# GateWay.net
KiCad netlist of a schematic drawn in EAGLE
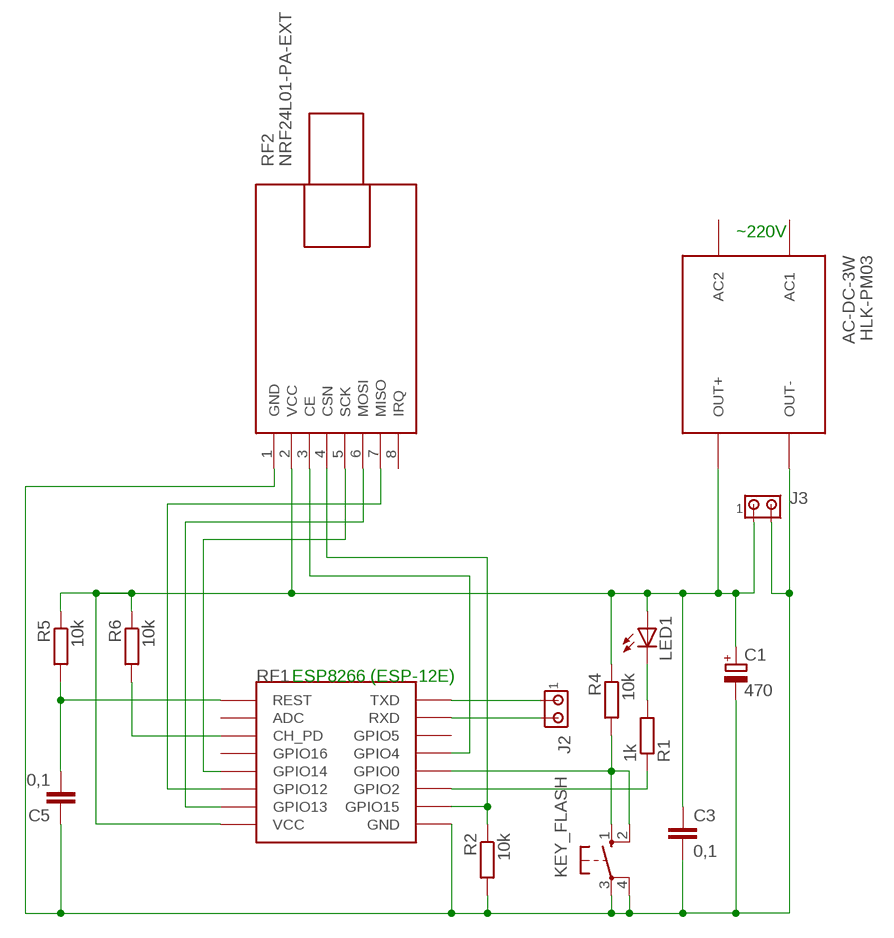
[diagram p0: schematic, sheet 1]

(export (version "E")
  (design (tool "Eeschema 10.0.6"))
  (components
    (comp (ref "C1")
      (value "470")
      (footprint "eagle-import:E2,5-6E")
      (libsource (lib "eagle-import") (part "CPOL-EUE2,5-6E"))
    )
    (comp (ref "C3")
      (value "0,1")
      (footprint "eagle-import:C025-024X044")
      (libsource (lib "eagle-import") (part "C-EU025-024X044"))
    )
    (comp (ref "C5")
      (value "0,1")
      (footprint "eagle-import:C025-025X050")
      (libsource (lib "eagle-import") (part "C-EU025-025X050"))
    )
    (comp (ref "HLK-PM03")
      (value "AC-DC-3W")
      (footprint "eagle-import:AC-DC-3.5W")
      (libsource (lib "eagle-import") (part "AC-DC-3.5W"))
    )
    (comp (ref "J2")
      (value "MTA02-100")
      (footprint "eagle-import:10X02MTA")
      (libsource (lib "eagle-import") (part "MTA02-100"))
    )
    (comp (ref "J3")
      (value "MTA02-100")
      (footprint "eagle-import:10X02MTA")
      (libsource (lib "eagle-import") (part "MTA02-100"))
    )
    (comp (ref "KEY_FLASH")
      (value "10-XX")
      (footprint "eagle-import:B3F-10XX")
      (fields (field (name "MPN") "B3F-1000"))
      (libsource (lib "eagle-import") (part "10-XX"))
    )
    (comp (ref "LED1")
      (value "LED5MM")
      (footprint "eagle-import:LED5MM")
      (libsource (lib "eagle-import") (part "LED5MM"))
    )
    (comp (ref "R1")
      (value "1k")
      (footprint "eagle-import:0204_7")
      (libsource (lib "eagle-import") (part "R-EU_0204/7"))
    )
    (comp (ref "R2")
      (value "10k")
      (footprint "eagle-import:0204_7")
      (libsource (lib "eagle-import") (part "R-EU_0204/7"))
    )
    (comp (ref "R4")
      (value "10k")
      (footprint "eagle-import:0204_7")
      (libsource (lib "eagle-import") (part "R-EU_0204/7"))
    )
    (comp (ref "R5")
      (value "10k")
      (footprint "eagle-import:0207_12")
      (libsource (lib "eagle-import") (part "R-EU_0207/12"))
    )
    (comp (ref "R6")
      (value "10k")
      (footprint "eagle-import:0207_10")
      (libsource (lib "eagle-import") (part "R-EU_0207/10"))
    )
    (comp (ref "RF1")
      (value "ESP")
      (footprint "eagle-import:ESP12E-SMD")
      (libsource (lib "eagle-import") (part "ESP12ESMD"))
    )
    (comp (ref "RF2")
      (value "NRF24L01-PA-EXT")
      (footprint "eagle-import:WIRELESS-NRF24L01-PA-EXT")
      (libsource (lib "eagle-import") (part "WIRELESS-NRF24L01-PA-EXT"))
    )
  )
  (nets
    (net (code "1") (name "Net-(HLK-PM03-OUT+)") (class "Default")
      (node (ref "C1") (pin "+") (pinfunction "+_+") (pintype "passive"))
      (node (ref "C3") (pin "1") (pinfunction "1_1") (pintype "passive"))
      (node (ref "HLK-PM03") (pin "J2.3") (pinfunction "OUT+_J2.3") (pintype "bidirectional"))
      (node (ref "J3") (pin "1") (pinfunction "1_1") (pintype "passive"))
      (node (ref "LED1") (pin "A") (pinfunction "A_A") (pintype "passive"))
      (node (ref "R4") (pin "1") (pinfunction "1_1") (pintype "passive"))
      (node (ref "R5") (pin "1") (pinfunction "1_1") (pintype "passive"))
      (node (ref "R6") (pin "1") (pinfunction "1_1") (pintype "passive"))
      (node (ref "RF1") (pin "VCC") (pinfunction "VCC_VCC") (pintype "bidirectional"))
      (node (ref "RF2") (pin "2") (pinfunction "VCC_2") (pintype "power_in"))
    )
    (net (code "2") (name "Net-(HLK-PM03-OUT-)") (class "Default")
      (node (ref "C1") (pin "-") (pinfunction "-_-") (pintype "passive"))
      (node (ref "C3") (pin "2") (pinfunction "2_2") (pintype "passive"))
      (node (ref "C5") (pin "1") (pinfunction "1_1") (pintype "passive"))
      (node (ref "HLK-PM03") (pin "J2.1") (pinfunction "OUT-_J2.1") (pintype "bidirectional"))
      (node (ref "J3") (pin "2") (pinfunction "2_2") (pintype "passive"))
      (node (ref "KEY_FLASH") (pin "3") (pinfunction "P_3") (pintype "passive"))
      (node (ref "KEY_FLASH") (pin "4") (pinfunction "P1_4") (pintype "passive"))
      (node (ref "R2") (pin "2") (pinfunction "2_2") (pintype "passive"))
      (node (ref "RF1") (pin "GND") (pinfunction "GND_GND") (pintype "bidirectional"))
      (node (ref "RF2") (pin "1") (pinfunction "GND_1") (pintype "power_in"))
    )
    (net (code "3") (name "Net-(KEY_FLASH-S)") (class "Default")
      (node (ref "KEY_FLASH") (pin "1") (pinfunction "S_1") (pintype "passive"))
      (node (ref "KEY_FLASH") (pin "2") (pinfunction "S1_2") (pintype "passive"))
      (node (ref "R4") (pin "2") (pinfunction "2_2") (pintype "passive"))
      (node (ref "RF1") (pin "GPIO0") (pinfunction "GPIO0_GPIO0") (pintype "bidirectional"))
    )
    (net (code "4") (name "Net-(LED1-C)") (class "Default")
      (node (ref "LED1") (pin "K") (pinfunction "C_K") (pintype "passive"))
      (node (ref "R1") (pin "2") (pinfunction "2_2") (pintype "passive"))
    )
    (net (code "5") (name "Net-(R1-Pad1)") (class "Default")
      (node (ref "R1") (pin "1") (pinfunction "1_1") (pintype "passive"))
      (node (ref "RF1") (pin "GPIO2") (pinfunction "GPIO2_GPIO2") (pintype "bidirectional"))
    )
    (net (code "6") (name "Net-(R6-Pad2)") (class "Default")
      (node (ref "R6") (pin "2") (pinfunction "2_2") (pintype "passive"))
      (node (ref "RF1") (pin "CH_PD") (pinfunction "CH_PD_CH_PD") (pintype "bidirectional"))
    )
    (net (code "7") (name "Net-(RF1-REST)") (class "Default")
      (node (ref "C5") (pin "2") (pinfunction "2_2") (pintype "passive"))
      (node (ref "R5") (pin "2") (pinfunction "2_2") (pintype "passive"))
      (node (ref "RF1") (pin "RESET") (pinfunction "REST_RESET") (pintype "bidirectional"))
    )
    (net (code "8") (name "Net-(RF1-RXD)") (class "Default")
      (node (ref "J2") (pin "2") (pinfunction "2_2") (pintype "passive"))
      (node (ref "RF1") (pin "RXD0") (pinfunction "RXD_RXD0") (pintype "bidirectional"))
    )
    (net (code "9") (name "Net-(RF1-TXD)") (class "Default")
      (node (ref "J2") (pin "1") (pinfunction "1_1") (pintype "passive"))
      (node (ref "RF1") (pin "TXD0") (pinfunction "TXD_TXD0") (pintype "bidirectional"))
    )
    (net (code "10") (name "Net-(RF2-CE)") (class "Default")
      (node (ref "RF1") (pin "GPIO4") (pinfunction "GPIO4_GPIO4") (pintype "bidirectional"))
      (node (ref "RF2") (pin "3") (pinfunction "CE_3") (pintype "bidirectional"))
    )
    (net (code "11") (name "Net-(RF2-CSN)") (class "Default")
      (node (ref "R2") (pin "1") (pinfunction "1_1") (pintype "passive"))
      (node (ref "RF1") (pin "GPIO15") (pinfunction "GPIO15_GPIO15") (pintype "bidirectional"))
      (node (ref "RF2") (pin "4") (pinfunction "CSN_4") (pintype "bidirectional"))
    )
    (net (code "12") (name "Net-(RF2-MISO)") (class "Default")
      (node (ref "RF1") (pin "GPIO12") (pinfunction "GPIO12_GPIO12") (pintype "bidirectional"))
      (node (ref "RF2") (pin "7") (pinfunction "MISO_7") (pintype "bidirectional"))
    )
    (net (code "13") (name "Net-(RF2-MOSI)") (class "Default")
      (node (ref "RF1") (pin "GPIO13") (pinfunction "GPIO13_GPIO13") (pintype "bidirectional"))
      (node (ref "RF2") (pin "6") (pinfunction "MOSI_6") (pintype "bidirectional"))
    )
    (net (code "14") (name "Net-(RF2-SCK)") (class "Default")
      (node (ref "RF1") (pin "GPIO14") (pinfunction "GPIO14_GPIO14") (pintype "bidirectional"))
      (node (ref "RF2") (pin "5") (pinfunction "SCK_5") (pintype "bidirectional"))
    )
    (net (code "15") (name "unconnected-(HLK-PM03-AC1-PadJ1.1)") (class "Default")
      (node (ref "HLK-PM03") (pin "J1.1") (pinfunction "AC1_J1.1") (pintype "bidirectional"))
    )
    (net (code "16") (name "unconnected-(HLK-PM03-AC2-PadJ1.2)") (class "Default")
      (node (ref "HLK-PM03") (pin "J1.2") (pinfunction "AC2_J1.2") (pintype "bidirectional"))
    )
    (net (code "17") (name "unconnected-(RF1-PadADC)") (class "Default")
      (node (ref "RF1") (pin "ADC") (pinfunction "ADC_ADC") (pintype "bidirectional"))
    )
    (net (code "18") (name "unconnected-(RF1-PadGPIO5)") (class "Default")
      (node (ref "RF1") (pin "GPIO5") (pinfunction "GPIO5_GPIO5") (pintype "bidirectional"))
    )
    (net (code "19") (name "unconnected-(RF1-PadGPIO16)") (class "Default")
      (node (ref "RF1") (pin "GPIO16") (pinfunction "GPIO16_GPIO16") (pintype "bidirectional"))
    )
    (net (code "20") (name "unconnected-(RF2-IRQ-Pad8)") (class "Default")
      (node (ref "RF2") (pin "8") (pinfunction "IRQ_8") (pintype "bidirectional"))
    )
  )
)
